# 1LD-20-mk-1_0_1.net
KiCad netlist of a schematic drawn in EAGLE
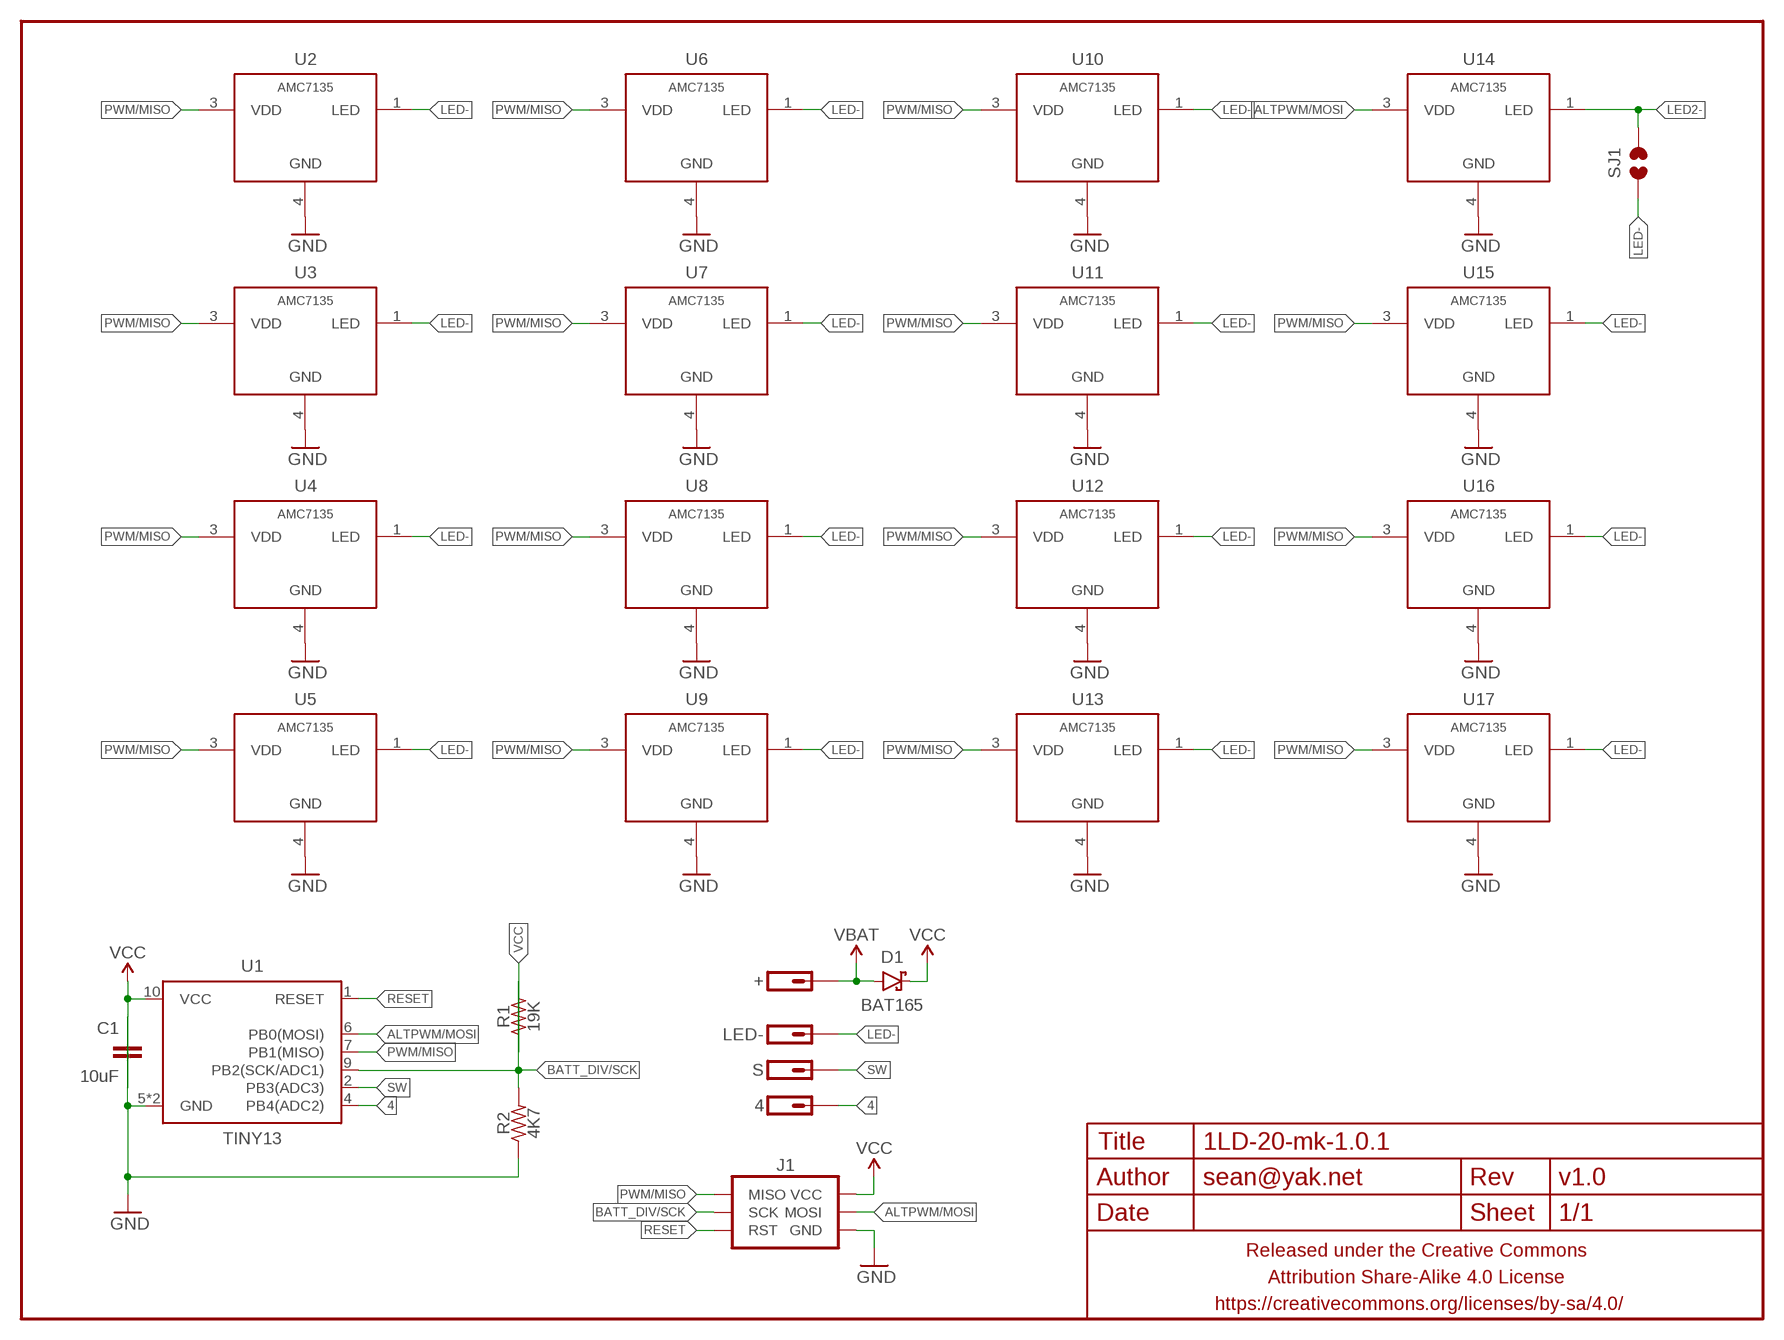
[diagram p0: schematic, sheet 1]

(export (version "E")
  (design (tool "Eeschema 10.0.6"))
  (components
    (comp (ref "+")
      (value "M01PTH-1.4MM")
      (footprint "eagle-import:1X01-1.4MM-CIR")
      (libsource (lib "eagle-import") (part "M01PTH-1.4MM"))
    )
    (comp (ref "4")
      (value "M01SMD-1MM-DIA-NS")
      (footprint "eagle-import:1X01-SMD-1MM-DIA-NS")
      (libsource (lib "eagle-import") (part "M01SMD-1MM-DIA-NS"))
    )
    (comp (ref "C1")
      (value "10uF")
      (footprint "eagle-import:C0402")
      (libsource (lib "eagle-import") (part "CAPACITOR-CERAMICC0402"))
    )
    (comp (ref "D1")
      (value "BAT165")
      (footprint "eagle-import:SOD323-SCHOTTKY")
      (libsource (lib "eagle-import") (part "DIODE-SCHOTTKYSOD323"))
    )
    (comp (ref "FRAME1")
      (value "FRAME-LETTERNO_PACKAGE")
      (footprint "eagle-import:DUMMY")
      (fields
        (field (name "DESIGNER") "sean@yak.net")
        (field (name "VERSION") "v1.0")
        (field (name "DESIGNER_1") "sean@yak.net")
        (field (name "VERSION_1") "v1.0")
      )
      (libsource (lib "eagle-import") (part "FRAME-LETTERNO_PACKAGE"))
    )
    (comp (ref "J1")
      (value "AVR_SPI_PRG_6SMD-1.27MM")
      (footprint "eagle-import:2X3-1.27MM-SMD")
      (libsource (lib "eagle-import") (part "AVR_SPI_PRG_6SMD-1.27MM"))
    )
    (comp (ref "LED-")
      (value "M01PTH-1MM-CIR-NS")
      (footprint "eagle-import:1X01-1MM-CIR-NS")
      (libsource (lib "eagle-import") (part "M01PTH-1MM-CIR-NS"))
    )
    (comp (ref "R1")
      (value "19K")
      (footprint "eagle-import:R0402")
      (libsource (lib "eagle-import") (part "RESISTORR0402"))
    )
    (comp (ref "R2")
      (value "4K7")
      (footprint "eagle-import:R0402")
      (libsource (lib "eagle-import") (part "RESISTORR0402"))
    )
    (comp (ref "S")
      (value "M01SMD-1MM-DIA-NS")
      (footprint "eagle-import:1X01-SMD-1MM-DIA-NS")
      (libsource (lib "eagle-import") (part "M01SMD-1MM-DIA-NS"))
    )
    (comp (ref "SJ1")
      (value "JUMPER-PAD-2-NOSMOL_NS")
      (footprint "eagle-import:PAD-JUMPER-2-NO_SMOL_NS")
      (libsource (lib "eagle-import") (part "JUMPER-PAD-2-NOSMOL_NS"))
    )
    (comp (ref "U1")
      (value "TINY13")
      (footprint "eagle-import:QFN10(2X5)")
      (libsource (lib "eagle-import") (part "ATTINY1310M1"))
    )
    (comp (ref "U2")
      (value "AMC7135")
      (footprint "eagle-import:SOT89-NOTHERM-ROUNDED-LESS")
      (libsource (lib "eagle-import") (part "AMC7135ROUNDED-LESS"))
    )
    (comp (ref "U3")
      (value "AMC7135")
      (footprint "eagle-import:SOT89-NOTHERM-ROUNDED-LESS")
      (libsource (lib "eagle-import") (part "AMC7135ROUNDED-LESS"))
    )
    (comp (ref "U4")
      (value "AMC7135")
      (footprint "eagle-import:SOT89-NOTHERM-ROUNDED-LESS")
      (libsource (lib "eagle-import") (part "AMC7135ROUNDED-LESS"))
    )
    (comp (ref "U5")
      (value "AMC7135")
      (footprint "eagle-import:SOT89-NOTHERM-ROUNDED-LESS")
      (libsource (lib "eagle-import") (part "AMC7135ROUNDED-LESS"))
    )
    (comp (ref "U6")
      (value "AMC7135")
      (footprint "eagle-import:SOT89-NOTHERM-ROUNDED-LESS")
      (libsource (lib "eagle-import") (part "AMC7135ROUNDED-LESS"))
    )
    (comp (ref "U7")
      (value "AMC7135")
      (footprint "eagle-import:SOT89-NOTHERM-ROUNDED-LESS")
      (libsource (lib "eagle-import") (part "AMC7135ROUNDED-LESS"))
    )
    (comp (ref "U8")
      (value "AMC7135")
      (footprint "eagle-import:SOT89-NOTHERM-ROUNDED-LESS")
      (libsource (lib "eagle-import") (part "AMC7135ROUNDED-LESS"))
    )
    (comp (ref "U9")
      (value "AMC7135")
      (footprint "eagle-import:SOT89-NOTHERM-ROUNDED-LESS")
      (libsource (lib "eagle-import") (part "AMC7135ROUNDED-LESS"))
    )
    (comp (ref "U10")
      (value "AMC7135")
      (footprint "eagle-import:SOT89-NOTHERM-ROUNDED-LESS")
      (libsource (lib "eagle-import") (part "AMC7135ROUNDED-LESS"))
    )
    (comp (ref "U11")
      (value "AMC7135")
      (footprint "eagle-import:SOT89-NOTHERM-ROUNDED-LESS")
      (libsource (lib "eagle-import") (part "AMC7135ROUNDED-LESS"))
    )
    (comp (ref "U12")
      (value "AMC7135")
      (footprint "eagle-import:SOT89-NOTHERM-ROUNDED-LESS")
      (libsource (lib "eagle-import") (part "AMC7135ROUNDED-LESS"))
    )
    (comp (ref "U13")
      (value "AMC7135")
      (footprint "eagle-import:SOT89-NOTHERM-ROUNDED-LESS")
      (libsource (lib "eagle-import") (part "AMC7135ROUNDED-LESS"))
    )
    (comp (ref "U14")
      (value "AMC7135")
      (footprint "eagle-import:SOT89-NOTHERM-ROUNDED-LESS")
      (libsource (lib "eagle-import") (part "AMC7135ROUNDED-LESS"))
    )
    (comp (ref "U15")
      (value "AMC7135")
      (footprint "eagle-import:SOT89-NOTHERM-ROUNDED-LESS")
      (libsource (lib "eagle-import") (part "AMC7135ROUNDED-LESS"))
    )
    (comp (ref "U16")
      (value "AMC7135")
      (footprint "eagle-import:SOT89-NOTHERM-ROUNDED-LESS")
      (libsource (lib "eagle-import") (part "AMC7135ROUNDED-LESS"))
    )
    (comp (ref "U17")
      (value "AMC7135")
      (footprint "eagle-import:SOT89-NOTHERM-ROUNDED-LESS")
      (libsource (lib "eagle-import") (part "AMC7135ROUNDED-LESS"))
    )
  )
  (nets
    (net (code "1") (name "4") (class "Default")
      (node (ref "4") (pin "P$1") (pinfunction "1_P$1") (pintype "passive"))
      (node (ref "U1") (pin "4") (pinfunction "PB4(ADC2)_4") (pintype "bidirectional"))
    )
    (net (code "2") (name "ALTPWM{slash}MOSI") (class "Default")
      (node (ref "J1") (pin "4") (pinfunction "MOSI_4") (pintype "passive"))
      (node (ref "U1") (pin "6") (pinfunction "PB0(MOSI)_6") (pintype "bidirectional"))
      (node (ref "U14") (pin "3") (pinfunction "VDD_3") (pintype "bidirectional"))
    )
    (net (code "3") (name "BATT_DIV{slash}SCK") (class "Default")
      (node (ref "J1") (pin "3") (pinfunction "SCK_3") (pintype "passive"))
      (node (ref "R1") (pin "2") (pinfunction "2_2") (pintype "passive"))
      (node (ref "R2") (pin "2") (pinfunction "2_2") (pintype "passive"))
      (node (ref "U1") (pin "9") (pinfunction "PB2(SCK/ADC1)_9") (pintype "bidirectional"))
    )
    (net (code "4") (name "GND") (class "Default")
      (node (ref "C1") (pin "1") (pinfunction "1_1") (pintype "passive"))
      (node (ref "J1") (pin "6") (pinfunction "GND_6") (pintype "passive"))
      (node (ref "R2") (pin "1") (pinfunction "1_1") (pintype "passive"))
      (node (ref "U1") (pin "5") (pinfunction "GND_5") (pintype "bidirectional"))
      (node (ref "U1") (pin "PAD") (pinfunction "GND_PAD") (pintype "bidirectional"))
      (node (ref "U10") (pin "4") (pinfunction "GND_4") (pintype "bidirectional"))
      (node (ref "U11") (pin "4") (pinfunction "GND_4") (pintype "bidirectional"))
      (node (ref "U12") (pin "4") (pinfunction "GND_4") (pintype "bidirectional"))
      (node (ref "U13") (pin "4") (pinfunction "GND_4") (pintype "bidirectional"))
      (node (ref "U14") (pin "4") (pinfunction "GND_4") (pintype "bidirectional"))
      (node (ref "U15") (pin "4") (pinfunction "GND_4") (pintype "bidirectional"))
      (node (ref "U16") (pin "4") (pinfunction "GND_4") (pintype "bidirectional"))
      (node (ref "U17") (pin "4") (pinfunction "GND_4") (pintype "bidirectional"))
      (node (ref "U2") (pin "4") (pinfunction "GND_4") (pintype "bidirectional"))
      (node (ref "U3") (pin "4") (pinfunction "GND_4") (pintype "bidirectional"))
      (node (ref "U4") (pin "4") (pinfunction "GND_4") (pintype "bidirectional"))
      (node (ref "U5") (pin "4") (pinfunction "GND_4") (pintype "bidirectional"))
      (node (ref "U6") (pin "4") (pinfunction "GND_4") (pintype "bidirectional"))
      (node (ref "U7") (pin "4") (pinfunction "GND_4") (pintype "bidirectional"))
      (node (ref "U8") (pin "4") (pinfunction "GND_4") (pintype "bidirectional"))
      (node (ref "U9") (pin "4") (pinfunction "GND_4") (pintype "bidirectional"))
    )
    (net (code "5") (name "LED-") (class "Default")
      (node (ref "LED-") (pin "1") (pinfunction "1_1") (pintype "passive"))
      (node (ref "SJ1") (pin "1") (pinfunction "1_1") (pintype "passive"))
      (node (ref "U10") (pin "1") (pinfunction "LED_1") (pintype "bidirectional"))
      (node (ref "U11") (pin "1") (pinfunction "LED_1") (pintype "bidirectional"))
      (node (ref "U12") (pin "1") (pinfunction "LED_1") (pintype "bidirectional"))
      (node (ref "U13") (pin "1") (pinfunction "LED_1") (pintype "bidirectional"))
      (node (ref "U15") (pin "1") (pinfunction "LED_1") (pintype "bidirectional"))
      (node (ref "U16") (pin "1") (pinfunction "LED_1") (pintype "bidirectional"))
      (node (ref "U17") (pin "1") (pinfunction "LED_1") (pintype "bidirectional"))
      (node (ref "U2") (pin "1") (pinfunction "LED_1") (pintype "bidirectional"))
      (node (ref "U3") (pin "1") (pinfunction "LED_1") (pintype "bidirectional"))
      (node (ref "U4") (pin "1") (pinfunction "LED_1") (pintype "bidirectional"))
      (node (ref "U5") (pin "1") (pinfunction "LED_1") (pintype "bidirectional"))
      (node (ref "U6") (pin "1") (pinfunction "LED_1") (pintype "bidirectional"))
      (node (ref "U7") (pin "1") (pinfunction "LED_1") (pintype "bidirectional"))
      (node (ref "U8") (pin "1") (pinfunction "LED_1") (pintype "bidirectional"))
      (node (ref "U9") (pin "1") (pinfunction "LED_1") (pintype "bidirectional"))
    )
    (net (code "6") (name "LED2-") (class "Default")
      (node (ref "SJ1") (pin "2") (pinfunction "2_2") (pintype "passive"))
      (node (ref "U14") (pin "1") (pinfunction "LED_1") (pintype "bidirectional"))
    )
    (net (code "7") (name "PWM{slash}MISO") (class "Default")
      (node (ref "J1") (pin "1") (pinfunction "MISO_1") (pintype "passive"))
      (node (ref "U1") (pin "7") (pinfunction "PB1(MISO)_7") (pintype "bidirectional"))
      (node (ref "U10") (pin "3") (pinfunction "VDD_3") (pintype "bidirectional"))
      (node (ref "U11") (pin "3") (pinfunction "VDD_3") (pintype "bidirectional"))
      (node (ref "U12") (pin "3") (pinfunction "VDD_3") (pintype "bidirectional"))
      (node (ref "U13") (pin "3") (pinfunction "VDD_3") (pintype "bidirectional"))
      (node (ref "U15") (pin "3") (pinfunction "VDD_3") (pintype "bidirectional"))
      (node (ref "U16") (pin "3") (pinfunction "VDD_3") (pintype "bidirectional"))
      (node (ref "U17") (pin "3") (pinfunction "VDD_3") (pintype "bidirectional"))
      (node (ref "U2") (pin "3") (pinfunction "VDD_3") (pintype "bidirectional"))
      (node (ref "U3") (pin "3") (pinfunction "VDD_3") (pintype "bidirectional"))
      (node (ref "U4") (pin "3") (pinfunction "VDD_3") (pintype "bidirectional"))
      (node (ref "U5") (pin "3") (pinfunction "VDD_3") (pintype "bidirectional"))
      (node (ref "U6") (pin "3") (pinfunction "VDD_3") (pintype "bidirectional"))
      (node (ref "U7") (pin "3") (pinfunction "VDD_3") (pintype "bidirectional"))
      (node (ref "U8") (pin "3") (pinfunction "VDD_3") (pintype "bidirectional"))
      (node (ref "U9") (pin "3") (pinfunction "VDD_3") (pintype "bidirectional"))
    )
    (net (code "8") (name "RESET") (class "Default")
      (node (ref "J1") (pin "5") (pinfunction "RST_5") (pintype "passive"))
      (node (ref "U1") (pin "1") (pinfunction "RESET_1") (pintype "bidirectional"))
    )
    (net (code "9") (name "SW") (class "Default")
      (node (ref "S") (pin "P$1") (pinfunction "1_P$1") (pintype "passive"))
      (node (ref "U1") (pin "2") (pinfunction "PB3(ADC3)_2") (pintype "bidirectional"))
    )
    (net (code "10") (name "VBAT") (class "Default")
      (node (ref "+") (pin "P$1") (pinfunction "1_P$1") (pintype "passive"))
      (node (ref "D1") (pin "A") (pinfunction "A_A") (pintype "passive"))
    )
    (net (code "11") (name "VCC") (class "Default")
      (node (ref "C1") (pin "2") (pinfunction "2_2") (pintype "passive"))
      (node (ref "D1") (pin "C") (pinfunction "C_C") (pintype "passive"))
      (node (ref "J1") (pin "2") (pinfunction "VCC_2") (pintype "passive"))
      (node (ref "R1") (pin "1") (pinfunction "1_1") (pintype "passive"))
      (node (ref "U1") (pin "10") (pinfunction "VCC_10") (pintype "bidirectional"))
    )
  )
)
